# LB_BIT_o16_LIGHTWIRE-v03_rev2.net
KiCad netlist of a schematic drawn in EAGLE
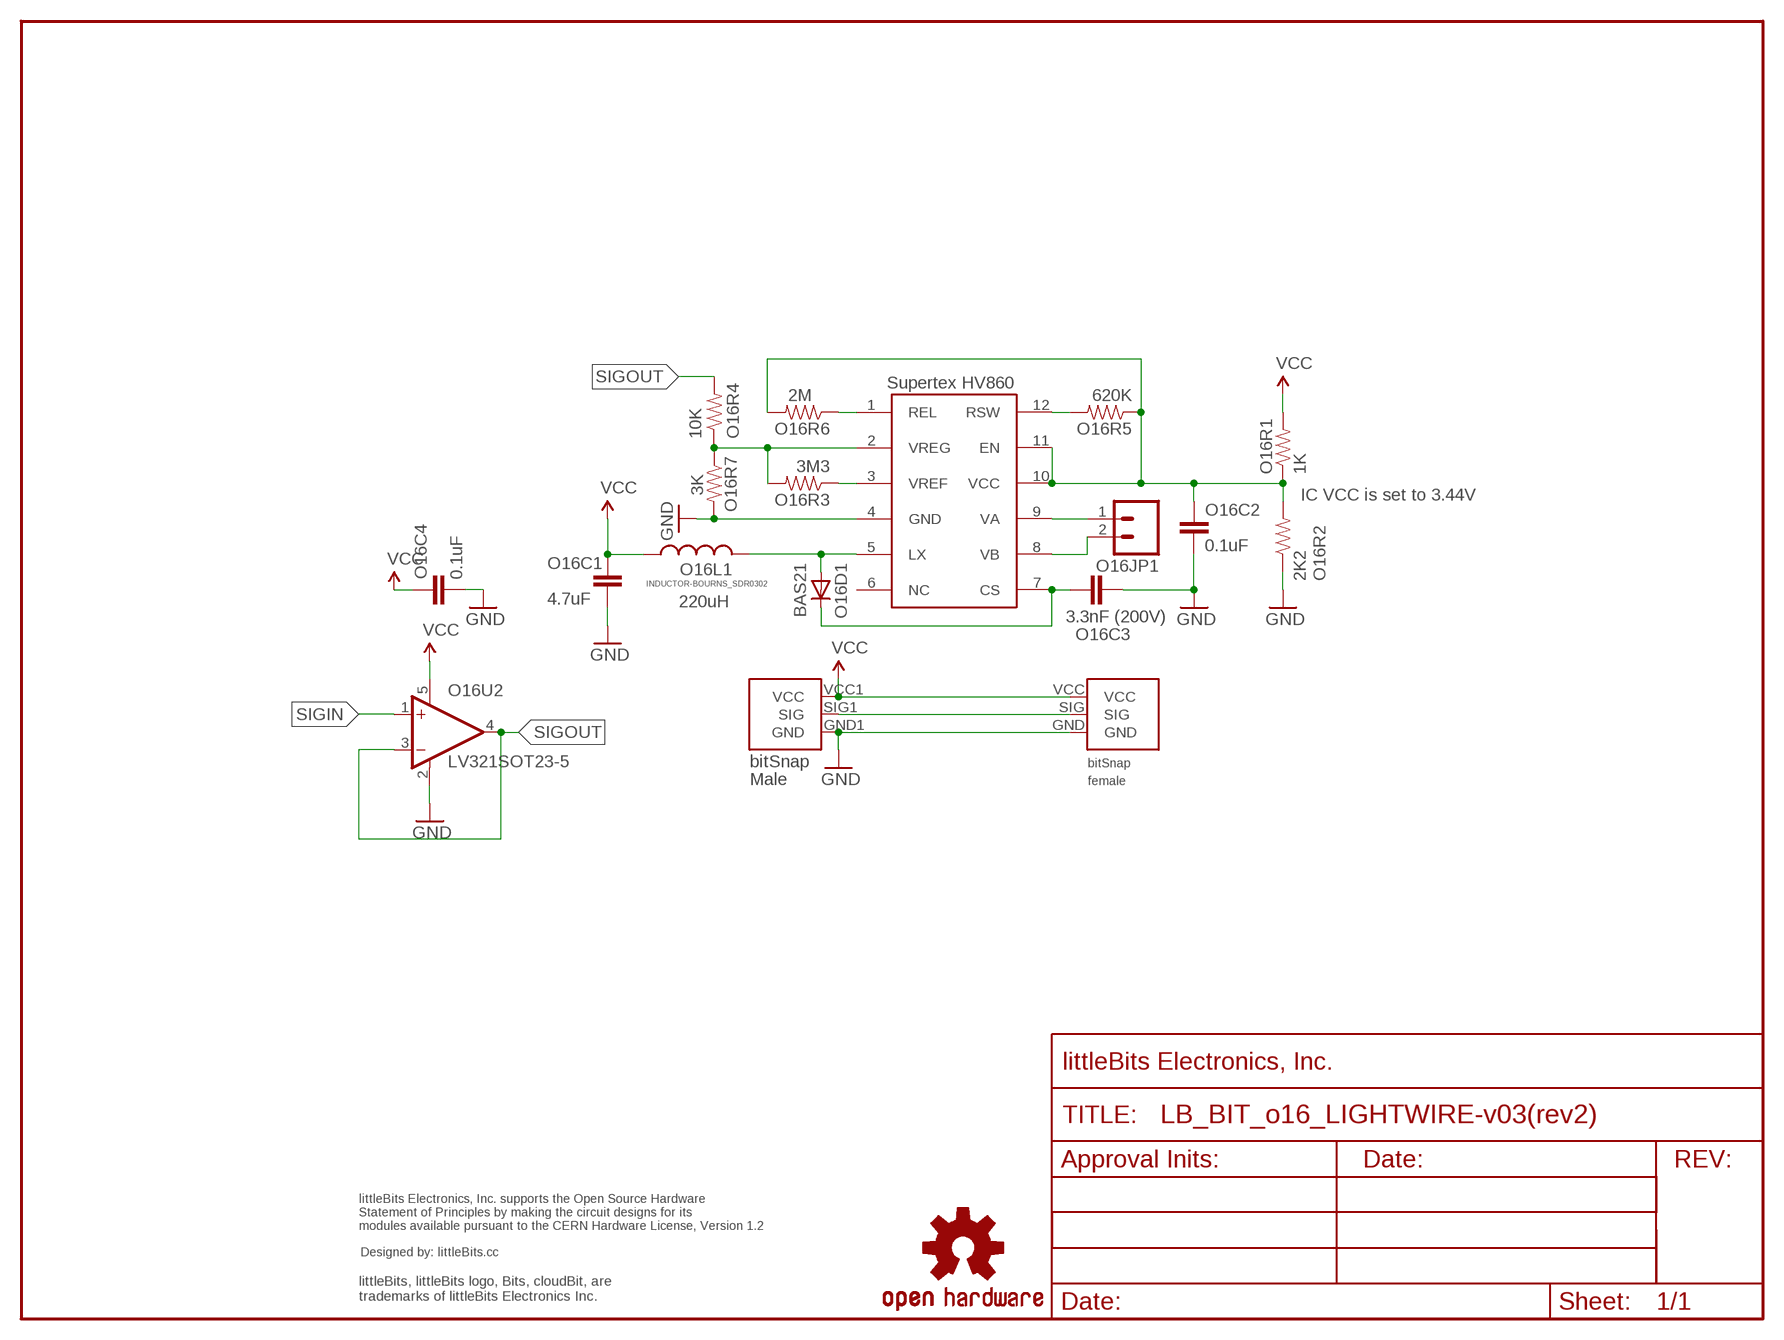
[diagram p0: schematic, sheet 1]

(export (version "E")
  (design (tool "Eeschema 10.0.6"))
  (components
    (comp (ref "O16BSF1")
      (value "BITSNAP_V03_FEMALE")
      (footprint "eagle-import:BITSNAP_V03_FEMALE")
      (libsource (lib "eagle-import") (part "BITSNAP_V03_FEMALE"))
    )
    (comp (ref "O16BSM1")
      (value "BITSNAP_V03_MALE")
      (footprint "eagle-import:BITSNAP_V03_MALE")
      (libsource (lib "eagle-import") (part "BITSNAP_V03_MALE"))
    )
    (comp (ref "O16C1")
      (value "4.7uF")
      (footprint "eagle-import:0603-CAP")
      (libsource (lib "eagle-import") (part "CAP0603-CAP"))
    )
    (comp (ref "O16C2")
      (value "0.1uF")
      (footprint "eagle-import:0603-CAP")
      (libsource (lib "eagle-import") (part "CAP0603-CAP"))
    )
    (comp (ref "O16C3")
      (value "3.3nF (200V)")
      (footprint "eagle-import:0805")
      (libsource (lib "eagle-import") (part "CAP0805"))
    )
    (comp (ref "O16C4")
      (value "0.1uF")
      (footprint "eagle-import:0603-CAP")
      (libsource (lib "eagle-import") (part "CAP0603-CAP"))
    )
    (comp (ref "O16D1")
      (value "BAS21")
      (footprint "eagle-import:SOD-323")
      (libsource (lib "eagle-import") (part "DIODESOD"))
    )
    (comp (ref "O16JP1")
      (value "M02-JST-2MM-SMT")
      (footprint "eagle-import:S2B-PH")
      (libsource (lib "eagle-import") (part "M02-JST-2MM-SMT"))
    )
    (comp (ref "O16L1")
      (value "INDUCTOR-BOURNS_SDR0302")
      (footprint "eagle-import:INDUCTOR-BOURNS_SDR0302")
      (libsource (lib "eagle-import") (part "INDUCTOR-BOURNS_SDR0302"))
    )
    (comp (ref "O16R1")
      (value "1K")
      (footprint "eagle-import:0603-RES")
      (libsource (lib "eagle-import") (part "RESISTOR0603-RES"))
    )
    (comp (ref "O16R2")
      (value "2K2")
      (footprint "eagle-import:0603-RES")
      (libsource (lib "eagle-import") (part "RESISTOR0603-RES"))
    )
    (comp (ref "O16R3")
      (value "3M3")
      (footprint "eagle-import:0603-RES")
      (libsource (lib "eagle-import") (part "RESISTOR0603-RES"))
    )
    (comp (ref "O16R4")
      (value "10K")
      (footprint "eagle-import:0603-RES")
      (libsource (lib "eagle-import") (part "RESISTOR0603-RES"))
    )
    (comp (ref "O16R5")
      (value "620K")
      (footprint "eagle-import:0603-RES")
      (libsource (lib "eagle-import") (part "RESISTOR0603-RES"))
    )
    (comp (ref "O16R6")
      (value "2M")
      (footprint "eagle-import:0603-RES")
      (libsource (lib "eagle-import") (part "RESISTOR0603-RES"))
    )
    (comp (ref "O16R7")
      (value "3K")
      (footprint "eagle-import:0603-RES")
      (libsource (lib "eagle-import") (part "RESISTOR0603-RES"))
    )
    (comp (ref "O16U1")
      (value "SUPERTEX-HV860")
      (footprint "eagle-import:QFN-12(K7)")
      (libsource (lib "eagle-import") (part "SUPERTEX-HV860"))
    )
    (comp (ref "O16U2")
      (value "LV321SOT23-5")
      (footprint "eagle-import:SOT23-5")
      (libsource (lib "eagle-import") (part "LV321SOT23-5"))
    )
    (comp (ref "U$1")
      (value "OSHW-LOGOL")
      (footprint "eagle-import:OSHW-LOGO-L")
      (libsource (lib "eagle-import") (part "OSHW-LOGOL"))
    )
    (comp (ref "U$2")
      (value "OSHWCREDIT")
      (footprint "eagle-import:OSHWCREDIT")
      (libsource (lib "eagle-import") (part "OSHWCREDIT"))
    )
    (comp (ref "U$5")
      (value "FRAME-LETTER-OHWOHW")
      (footprint "eagle-import:FABDWG01-OHW")
      (libsource (lib "eagle-import") (part "FRAME-LETTER-OHWOHW"))
    )
  )
  (nets
    (net (code "1") (name "GND") (class "Default")
      (node (ref "O16BSF1") (pin "GND") (pinfunction "GND_GND") (pintype "bidirectional"))
      (node (ref "O16BSM1") (pin "GND1") (pinfunction "GND_GND1") (pintype "bidirectional"))
      (node (ref "O16C1") (pin "2") (pinfunction "2_2") (pintype "passive"))
      (node (ref "O16C2") (pin "2") (pinfunction "2_2") (pintype "passive"))
      (node (ref "O16C3") (pin "2") (pinfunction "2_2") (pintype "passive"))
      (node (ref "O16C4") (pin "2") (pinfunction "2_2") (pintype "passive"))
      (node (ref "O16R2") (pin "1") (pinfunction "1_1") (pintype "passive"))
      (node (ref "O16R7") (pin "2") (pinfunction "2_2") (pintype "passive"))
      (node (ref "O16U1") (pin "4") (pinfunction "GND_4") (pintype "bidirectional"))
      (node (ref "O16U2") (pin "2") (pinfunction "V-_2") (pintype "power_in"))
    )
    (net (code "2") (name "Net-(O16D1-A)") (class "Default")
      (node (ref "O16D1") (pin "2") (pinfunction "A_2") (pintype "passive"))
      (node (ref "O16L1") (pin "2") (pinfunction "2_2") (pintype "passive"))
      (node (ref "O16U1") (pin "5") (pinfunction "LX_5") (pintype "bidirectional"))
    )
    (net (code "3") (name "Net-(O16D1-C)") (class "Default")
      (node (ref "O16C3") (pin "1") (pinfunction "1_1") (pintype "passive"))
      (node (ref "O16D1") (pin "1") (pinfunction "C_1") (pintype "passive"))
      (node (ref "O16U1") (pin "7") (pinfunction "CS_7") (pintype "bidirectional"))
    )
    (net (code "4") (name "Net-(O16U1-EN)") (class "Default")
      (node (ref "O16C2") (pin "1") (pinfunction "1_1") (pintype "passive"))
      (node (ref "O16R1") (pin "1") (pinfunction "1_1") (pintype "passive"))
      (node (ref "O16R2") (pin "2") (pinfunction "2_2") (pintype "passive"))
      (node (ref "O16R5") (pin "1") (pinfunction "1_1") (pintype "passive"))
      (node (ref "O16R6") (pin "2") (pinfunction "2_2") (pintype "passive"))
      (node (ref "O16U1") (pin "10") (pinfunction "VCC_10") (pintype "bidirectional"))
      (node (ref "O16U1") (pin "11") (pinfunction "EN_11") (pintype "bidirectional"))
    )
    (net (code "5") (name "Net-(O16U1-REL)") (class "Default")
      (node (ref "O16R6") (pin "1") (pinfunction "1_1") (pintype "passive"))
      (node (ref "O16U1") (pin "1") (pinfunction "REL_1") (pintype "bidirectional"))
    )
    (net (code "6") (name "Net-(O16U1-RSW)") (class "Default")
      (node (ref "O16R5") (pin "2") (pinfunction "2_2") (pintype "passive"))
      (node (ref "O16U1") (pin "12") (pinfunction "RSW_12") (pintype "bidirectional"))
    )
    (net (code "7") (name "Net-(O16U1-VA)") (class "Default")
      (node (ref "O16JP1") (pin "1") (pinfunction "1_1") (pintype "passive"))
      (node (ref "O16U1") (pin "9") (pinfunction "VA_9") (pintype "bidirectional"))
    )
    (net (code "8") (name "Net-(O16U1-VB)") (class "Default")
      (node (ref "O16JP1") (pin "2") (pinfunction "2_2") (pintype "passive"))
      (node (ref "O16U1") (pin "8") (pinfunction "VB_8") (pintype "bidirectional"))
    )
    (net (code "9") (name "Net-(O16U1-VREF)") (class "Default")
      (node (ref "O16R3") (pin "1") (pinfunction "1_1") (pintype "passive"))
      (node (ref "O16U1") (pin "3") (pinfunction "VREF_3") (pintype "bidirectional"))
    )
    (net (code "10") (name "Net-(O16U1-VREG)") (class "Default")
      (node (ref "O16R3") (pin "2") (pinfunction "2_2") (pintype "passive"))
      (node (ref "O16R4") (pin "1") (pinfunction "1_1") (pintype "passive"))
      (node (ref "O16R7") (pin "1") (pinfunction "1_1") (pintype "passive"))
      (node (ref "O16U1") (pin "2") (pinfunction "VREG_2") (pintype "bidirectional"))
    )
    (net (code "11") (name "SIGIN") (class "Default")
      (node (ref "O16BSF1") (pin "SIG") (pinfunction "SIG_SIG") (pintype "bidirectional"))
      (node (ref "O16BSM1") (pin "SIG1") (pinfunction "SIG_SIG1") (pintype "bidirectional"))
      (node (ref "O16U2") (pin "1") (pinfunction "+IN_1") (pintype "input"))
    )
    (net (code "12") (name "SIGOUT") (class "Default")
      (node (ref "O16R4") (pin "2") (pinfunction "2_2") (pintype "passive"))
      (node (ref "O16U2") (pin "3") (pinfunction "-IN_3") (pintype "input"))
      (node (ref "O16U2") (pin "4") (pinfunction "OUT_4") (pintype "output"))
    )
    (net (code "13") (name "VCC") (class "Default")
      (node (ref "O16BSF1") (pin "VCC") (pinfunction "VCC_VCC") (pintype "bidirectional"))
      (node (ref "O16BSM1") (pin "VCC1") (pinfunction "VCC_VCC1") (pintype "bidirectional"))
      (node (ref "O16C1") (pin "1") (pinfunction "1_1") (pintype "passive"))
      (node (ref "O16C4") (pin "1") (pinfunction "1_1") (pintype "passive"))
      (node (ref "O16L1") (pin "1") (pinfunction "1_1") (pintype "passive"))
      (node (ref "O16R1") (pin "2") (pinfunction "2_2") (pintype "passive"))
      (node (ref "O16U2") (pin "5") (pinfunction "V+_5") (pintype "power_in"))
    )
    (net (code "14") (name "unconnected-(O16U1-NC-Pad6)") (class "Default")
      (node (ref "O16U1") (pin "6") (pinfunction "NC_6") (pintype "bidirectional"))
    )
  )
)
